# 01-multimodal-powersupply-connections.net
KiCad netlist of a schematic drawn in Altium Designer
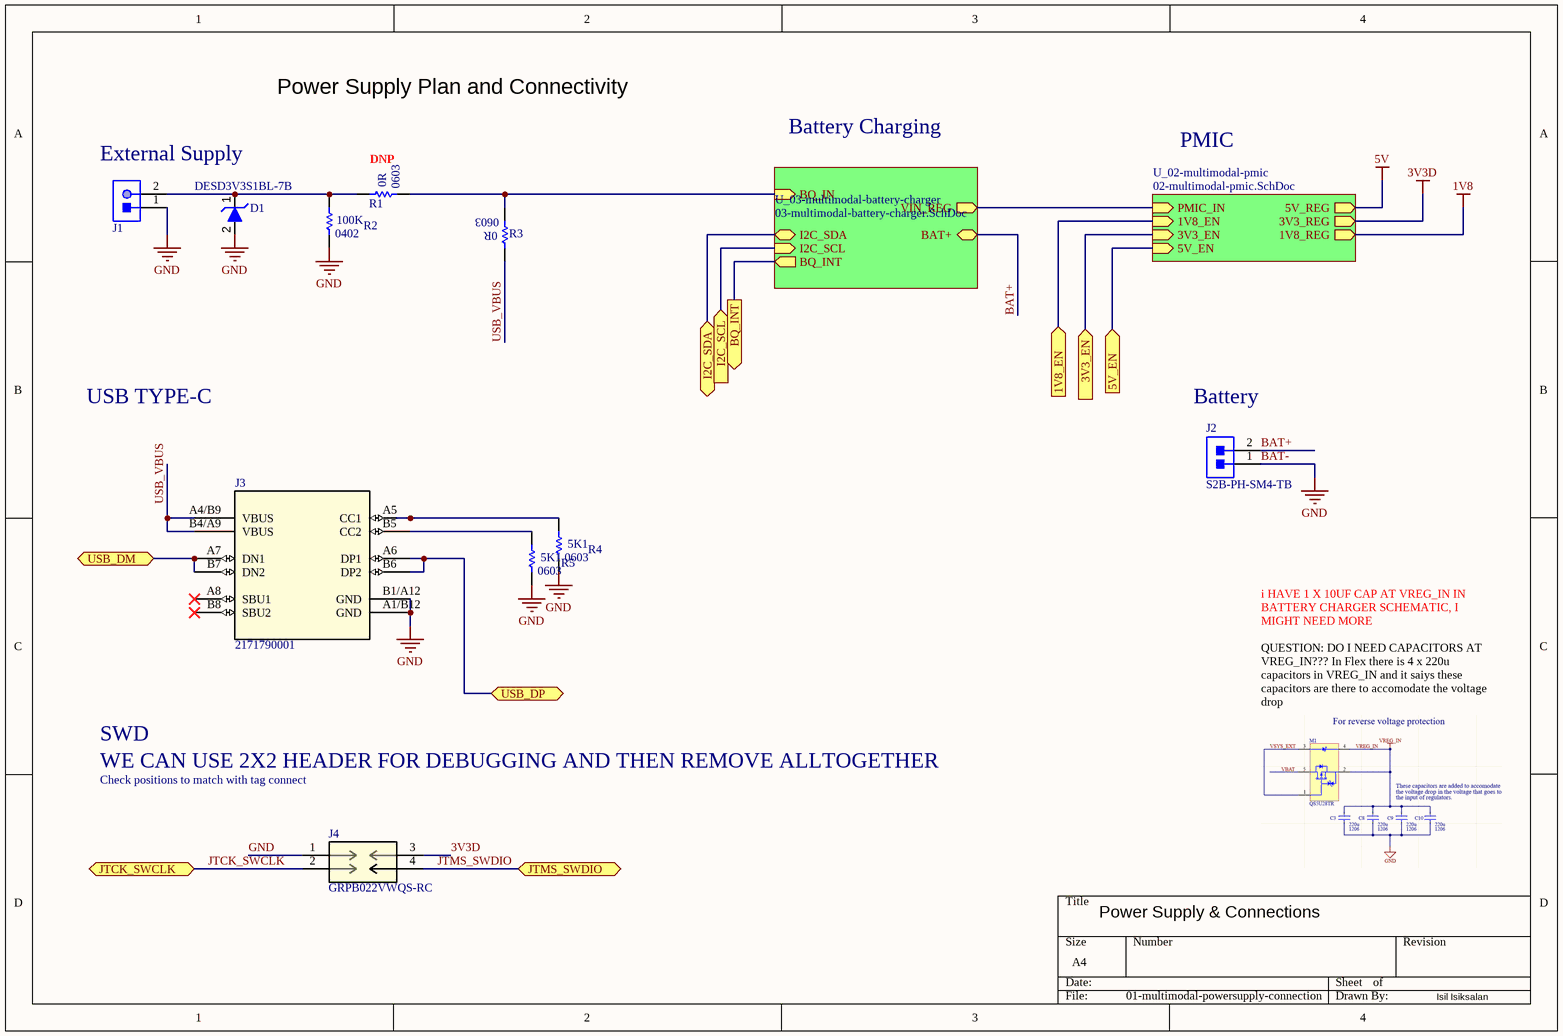
[diagram p0: 01-multimodal-powersupply-connections.SchDoc]

(export (version "E")
  (design (tool "Eeschema 10.0.6"))
  (components
    (comp (ref "D1")
      (value "DESD3V3S1BL-7B")
      (footprint "TVSDIODE-0402")
      (description "TVS DIODE 3.3V 7V DFN1006-2")
      (fields (field (name "MANUFACTURER") "Diodes"))
      (libsource (lib "multimodal") (part "DESD3V3S1BL-7B"))
    )
    (comp (ref "J1")
      (value "TH-Connector")
      (footprint "2-PIN-TH-CONN")
      (description "Power Connector")
      (libsource (lib "multimodal") (part "TH-Connector"))
    )
    (comp (ref "J2")
      (value "S2B-PH-SM4-TB")
      (footprint "2-PIN-SMD-CONN-2-MM-PITCH")
      (description "CONN HEADER SMD R/A 2POS 2MM")
      (fields (field (name "MANUFACTURER") "JST"))
      (libsource (lib "multimodal") (part "S2B-PH-SM4-TB"))
    )
    (comp (ref "J3")
      (value "2171790001")
      (footprint "2171790001_MOL")
      (fields (field (name "COPYRIGHT") "Copyright (C) 2025 Ultra Librarian. All rights reserved."))
      (libsource (lib "multimodal") (part "2171790001"))
    )
    (comp (ref "J4")
      (value "GRPB022VWQS-RC")
      (footprint "CON4_GRPB022VWQS-RC_SUL")
      (description "Description")
      (fields (field (name "COPYRIGHT") "Copyright (C) 2025 Ultra Librarian. All rights reserved."))
      (libsource (lib "multimodal") (part "GRPB022VWQS-RC"))
    )
    (comp (ref "R1")
      (value "RMCF0603ZT0R00")
      (footprint "RES-STACK-POLE-0603")
      (description "RES 0 OHM JUMPER 1/10W 0603")
      (libsource (lib "multimodal") (part "RMCF0603ZT0R00"))
    )
    (comp (ref "R2")
      (value "RMCF0402FT100K")
      (footprint "RES-STACK-POLE-0402")
      (description "RES 100K OHM 1% 1/16W 0402")
      (libsource (lib "multimodal") (part "RMCF0402FT100K"))
    )
    (comp (ref "R3")
      (value "RMCF0603ZT0R00")
      (footprint "RES-STACK-POLE-0603")
      (description "RES 0 OHM JUMPER 1/10W 0603")
      (libsource (lib "multimodal") (part "RMCF0603ZT0R00"))
    )
    (comp (ref "R4")
      (value "RMCF0603FT5K10")
      (footprint "RES-STACK-POLE-0603")
      (description "RES 5.1K OHM 1% 1/10W 0603")
      (libsource (lib "multimodal") (part "RMCF0603FT5K10"))
    )
    (comp (ref "R5")
      (value "RMCF0603FT5K10")
      (footprint "RES-STACK-POLE-0603")
      (description "RES 5.1K OHM 1% 1/10W 0603")
      (libsource (lib "multimodal") (part "RMCF0603FT5K10"))
    )
  )
  (nets
    (net (code "4") (name "/BAT+") (class "Default")
      (node (ref "J2") (pin "2") (pinfunction "2_2") (pintype "passive"))
    )
    (net (code "5") (name "/BQ_IN") (class "Default")
      (node (ref "R1") (pin "1") (pinfunction "1_1") (pintype "passive"))
      (node (ref "R3") (pin "1") (pinfunction "1_1") (pintype "passive"))
    )
    (net (code "9") (name "/JTCK_SWCLK") (class "Default")
      (node (ref "J4") (pin "2") (pinfunction "2_2") (pintype "passive"))
    )
    (net (code "10") (name "/JTMS_SWDIO") (class "Default")
      (node (ref "J4") (pin "4") (pinfunction "4_4") (pintype "passive"))
    )
    (net (code "11") (name "/USB_DM") (class "Default")
      (node (ref "J3") (pin "A7") (pinfunction "DN1_A7") (pintype "bidirectional"))
      (node (ref "J3") (pin "B7") (pinfunction "DN2_B7") (pintype "bidirectional"))
    )
    (net (code "12") (name "/USB_DP") (class "Default")
      (node (ref "J3") (pin "A6") (pinfunction "DP1_A6") (pintype "bidirectional"))
      (node (ref "J3") (pin "B6") (pinfunction "DP2_B6") (pintype "bidirectional"))
    )
    (net (code "13") (name "/USB_VBUS") (class "Default")
      (node (ref "J3") (pin "A4/B9") (pinfunction "VBUS_A4/B9") (pintype "power_in"))
      (node (ref "J3") (pin "B4/A9") (pinfunction "VBUS_B4/A9") (pintype "power_in"))
      (node (ref "R3") (pin "2") (pinfunction "2_2") (pintype "passive"))
    )
    (net (code "16") (name "3V3D") (class "Default")
      (node (ref "J4") (pin "3") (pinfunction "3_3") (pintype "passive"))
    )
    (net (code "18") (name "GND") (class "Default")
      (node (ref "D1") (pin "2") (pintype "passive"))
      (node (ref "J1") (pin "1") (pinfunction "1_1") (pintype "passive"))
      (node (ref "J2") (pin "1") (pinfunction "1_1") (pintype "passive"))
      (node (ref "J3") (pin "A1/B12") (pinfunction "GND_A1/B12") (pintype "power_in"))
      (node (ref "J3") (pin "B1/A12") (pinfunction "GND_B1/A12") (pintype "power_in"))
      (node (ref "J4") (pin "1") (pinfunction "1_1") (pintype "passive"))
      (node (ref "R2") (pin "1") (pinfunction "1_1") (pintype "passive"))
      (node (ref "R4") (pin "1") (pinfunction "1_1") (pintype "passive"))
      (node (ref "R5") (pin "1") (pinfunction "1_1") (pintype "passive"))
    )
    (net (code "19") (name "Net-(D1-Pad1)") (class "Default")
      (node (ref "D1") (pin "1") (pintype "passive"))
      (node (ref "J1") (pin "2") (pinfunction "2_2") (pintype "passive"))
      (node (ref "R1") (pin "2") (pinfunction "2_2") (pintype "passive"))
      (node (ref "R2") (pin "2") (pinfunction "2_2") (pintype "passive"))
    )
    (net (code "20") (name "Net-(J3-CC1)") (class "Default")
      (node (ref "J3") (pin "A5") (pinfunction "CC1_A5") (pintype "bidirectional"))
      (node (ref "R4") (pin "2") (pinfunction "2_2") (pintype "passive"))
    )
    (net (code "21") (name "Net-(J3-CC2)") (class "Default")
      (node (ref "J3") (pin "B5") (pinfunction "CC2_B5") (pintype "bidirectional"))
      (node (ref "R5") (pin "2") (pinfunction "2_2") (pintype "passive"))
    )
    (net (code "22") (name "unconnected-(J3-SBU1-PadA8)") (class "Default")
      (node (ref "J3") (pin "A8") (pinfunction "SBU1_A8") (pintype "bidirectional+no_connect"))
    )
    (net (code "23") (name "unconnected-(J3-SBU2-PadB8)") (class "Default")
      (node (ref "J3") (pin "B8") (pinfunction "SBU2_B8") (pintype "bidirectional+no_connect"))
    )
  )
)
